# Fubarino_SD_v10.net
KiCad netlist of a schematic drawn in EAGLE
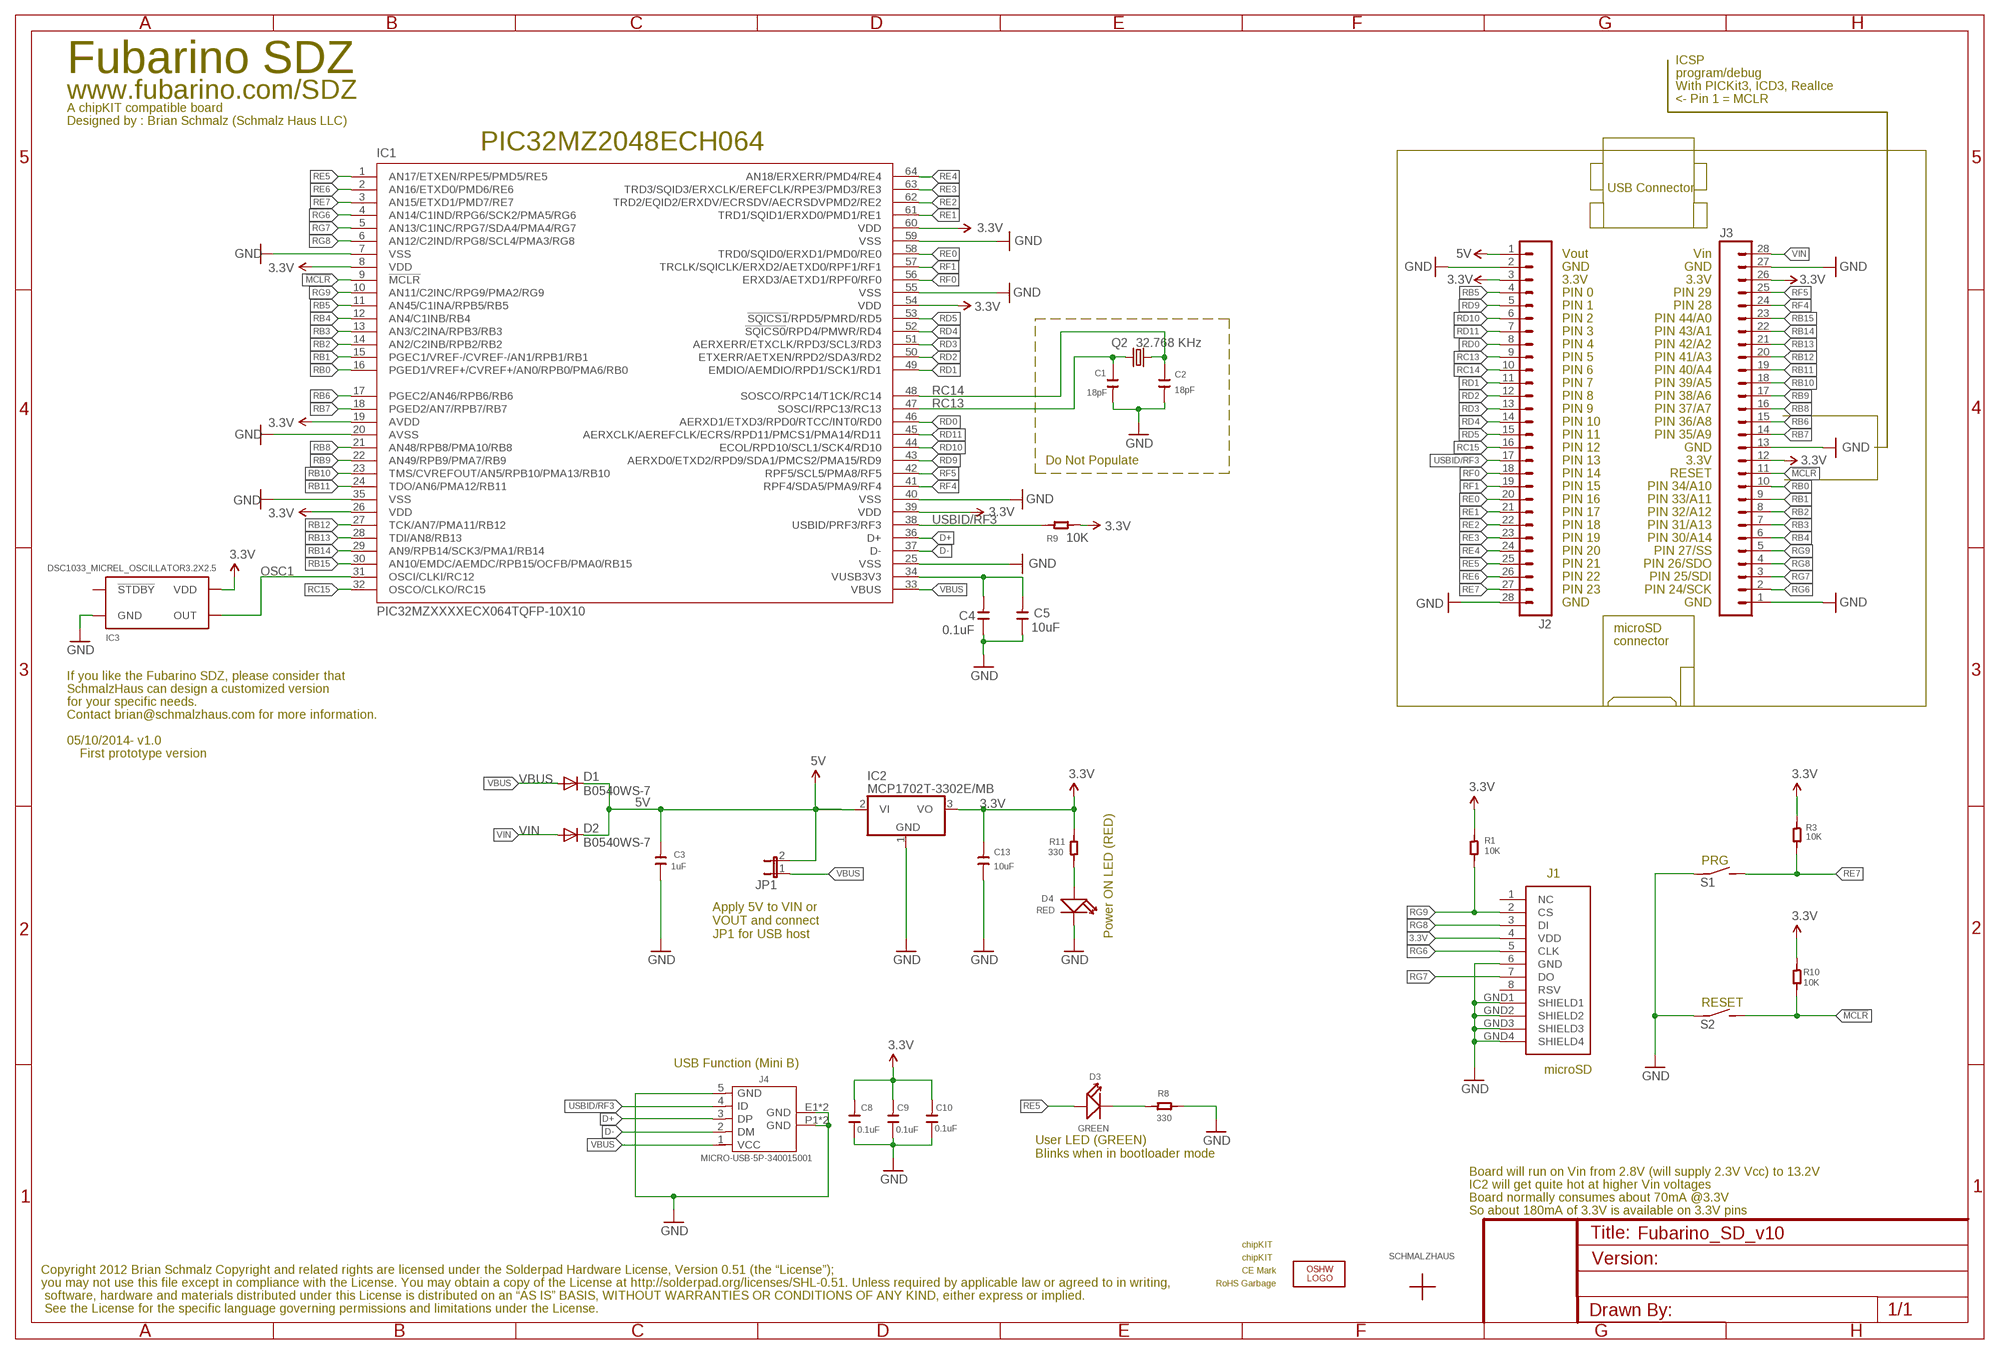
[diagram p0: schematic, sheet 1]

(export (version "E")
  (design (tool "Eeschema 10.0.6"))
  (components
    (comp (ref "C1")
      (value "18pF")
      (footprint "eagle-import:C0603")
      (libsource (lib "eagle-import") (part "C-0603"))
    )
    (comp (ref "C2")
      (value "18pF")
      (footprint "eagle-import:C0603")
      (libsource (lib "eagle-import") (part "C-0603"))
    )
    (comp (ref "C3")
      (value "1uF")
      (footprint "eagle-import:C0603")
      (libsource (lib "eagle-import") (part "C-0603"))
    )
    (comp (ref "C4")
      (value "0.1uF")
      (footprint "eagle-import:C0603")
      (libsource (lib "eagle-import") (part "C-0603"))
    )
    (comp (ref "C5")
      (value "10uF")
      (footprint "eagle-import:C0805")
      (libsource (lib "eagle-import") (part "C-0805"))
    )
    (comp (ref "C8")
      (value "0.1uF")
      (footprint "eagle-import:C0603")
      (libsource (lib "eagle-import") (part "C-0603"))
    )
    (comp (ref "C9")
      (value "0.1uF")
      (footprint "eagle-import:C0603")
      (libsource (lib "eagle-import") (part "C-0603"))
    )
    (comp (ref "C10")
      (value "0.1uF")
      (footprint "eagle-import:C0603")
      (libsource (lib "eagle-import") (part "C-0603"))
    )
    (comp (ref "C13")
      (value "10uF")
      (footprint "eagle-import:C0805")
      (libsource (lib "eagle-import") (part "C-0805"))
    )
    (comp (ref "D1")
      (value "B0540WS-7")
      (footprint "eagle-import:SOD-323")
      (libsource (lib "eagle-import") (part "DIODESOD"))
    )
    (comp (ref "D2")
      (value "B0540WS-7")
      (footprint "eagle-import:SOD-323")
      (libsource (lib "eagle-import") (part "DIODESOD"))
    )
    (comp (ref "D3")
      (value "GREEN")
      (footprint "eagle-import:LED0603")
      (libsource (lib "eagle-import") (part "LED"))
    )
    (comp (ref "D4")
      (value "RED")
      (footprint "eagle-import:LED0603")
      (libsource (lib "eagle-import") (part "LED"))
    )
    (comp (ref "IC1")
      (value "PIC32MZXXXXECX064TQFP-10X10")
      (footprint "eagle-import:TQFP64-10X10-SOLDERDAMS")
      (libsource (lib "eagle-import") (part "PIC32MZXXXXECX064TQFP-10X10"))
    )
    (comp (ref "IC2")
      (value "MCP1702T-3302E/MB")
      (footprint "eagle-import:SOT89")
      (libsource (lib "eagle-import") (part "MCP1703MB33"))
    )
    (comp (ref "IC3")
      (value "DSC1033_MICREL_OSCILLATOR3.2X2.5")
      (footprint "eagle-import:3.2X2.5_SILABS_OSC_DSC1033")
      (libsource (lib "eagle-import") (part "DSC1033_MICREL_OSCILLATOR3.2X2.5"))
    )
    (comp (ref "J1")
      (value "MICRO_SD_CARD_SOCKET")
      (footprint "eagle-import:SD-MMC_SOCKET-PP")
      (libsource (lib "eagle-import") (part "MICRO_SD_CARD_SOCKET"))
    )
    (comp (ref "J2")
      (value "M28USEPIN1")
      (footprint "eagle-import:1X28")
      (libsource (lib "eagle-import") (part "M28USEPIN1"))
    )
    (comp (ref "J3")
      (value "M28NOPIN1")
      (footprint "eagle-import:1X28_NO_PIN_1")
      (libsource (lib "eagle-import") (part "M28NOPIN1"))
    )
    (comp (ref "J4")
      (value "MICRO-USB-5P-340015001")
      (footprint "eagle-import:B-SMD-5P")
      (libsource (lib "eagle-import") (part "MICRO-USB-5P-340015001"))
    )
    (comp (ref "JP1")
      (value "JUMPER-2SMD-NO")
      (footprint "eagle-import:SJ_2S-NO")
      (libsource (lib "eagle-import") (part "JUMPER-2SMD-NO"))
    )
    (comp (ref "LOGO1")
      (value "OSHW_LOGO_8MILX0070-NT")
      (footprint "eagle-import:OSHW_8X70_NOTEXT")
      (libsource (lib "eagle-import") (part "OSHW_LOGO_8MILX0070-NT"))
    )
    (comp (ref "Q2")
      (value "32.768 KHz")
      (footprint "eagle-import:TC26H")
      (libsource (lib "eagle-import") (part "CRYSTALTC26H"))
    )
    (comp (ref "R1")
      (value "10K")
      (footprint "eagle-import:R0603")
      (libsource (lib "eagle-import") (part "R-0603"))
    )
    (comp (ref "R3")
      (value "10K")
      (footprint "eagle-import:R0603")
      (libsource (lib "eagle-import") (part "R-0603"))
    )
    (comp (ref "R8")
      (value "330")
      (footprint "eagle-import:R0603")
      (libsource (lib "eagle-import") (part "R-0603"))
    )
    (comp (ref "R9")
      (value "10K")
      (footprint "eagle-import:R0603")
      (libsource (lib "eagle-import") (part "R-0603"))
    )
    (comp (ref "R10")
      (value "10K")
      (footprint "eagle-import:R0603")
      (libsource (lib "eagle-import") (part "R-0603"))
    )
    (comp (ref "R11")
      (value "330")
      (footprint "eagle-import:R0603")
      (libsource (lib "eagle-import") (part "R-0603"))
    )
    (comp (ref "S1")
      (value "SWITCH")
      (footprint "eagle-import:SWITCH_KMR_SMT_TACT")
      (libsource (lib "eagle-import") (part "SWITCH"))
    )
    (comp (ref "S2")
      (value "SWITCH")
      (footprint "eagle-import:SWITCH_KMR_SMT_TACT")
      (libsource (lib "eagle-import") (part "SWITCH"))
    )
    (comp (ref "U$1")
      (value "SCHMALZHAUSSCHMALZHAUS_SMALL")
      (footprint "eagle-import:SCHMALZHAUS_SMALL")
      (libsource (lib "eagle-import") (part "SCHMALZHAUSSCHMALZHAUS_SMALL"))
    )
    (comp (ref "U$2")
      (value "CE_MARK5MM")
      (footprint "eagle-import:CE_5MM")
      (libsource (lib "eagle-import") (part "CE_MARK5MM"))
    )
    (comp (ref "U$3")
      (value "ROHS_GARBAGE")
      (footprint "eagle-import:ROHS_GARBAGE_5MM")
      (libsource (lib "eagle-import") (part "ROHS_GARBAGE"))
    )
    (comp (ref "U$4")
      (value "CHIPKIT2MM")
      (footprint "eagle-import:CHIPKIT_2MM")
      (libsource (lib "eagle-import") (part "CHIPKIT2MM"))
    )
    (comp (ref "U$5")
      (value "CHIPKIT2MM")
      (footprint "eagle-import:CHIPKIT_2MM")
      (libsource (lib "eagle-import") (part "CHIPKIT2MM"))
    )
  )
  (nets
    (net (code "1") (name "/OSC1") (class "Default")
      (node (ref "IC1") (pin "31") (pinfunction "OSCI/CLKI/RC12_31") (pintype "bidirectional"))
      (node (ref "IC3") (pin "P$3") (pinfunction "OUT_P$3") (pintype "output"))
    )
    (net (code "2") (name "/~{MCLR}") (class "Default")
      (node (ref "IC1") (pin "9") (pinfunction "~{MCLR}_9") (pintype "input"))
      (node (ref "J3") (pin "11") (pinfunction "11_11") (pintype "passive"))
      (node (ref "R10") (pin "2") (pinfunction "2_2") (pintype "bidirectional"))
      (node (ref "S2") (pin "P$3") (pinfunction "2_P$3") (pintype "passive"))
      (node (ref "S2") (pin "P$4") (pinfunction "2_P$4") (pintype "passive"))
    )
    (net (code "3") (name "3.3V") (class "Default")
      (node (ref "C10") (pin "1") (pinfunction "1_1") (pintype "bidirectional"))
      (node (ref "C13") (pin "1") (pinfunction "1_1") (pintype "bidirectional"))
      (node (ref "C8") (pin "1") (pinfunction "1_1") (pintype "bidirectional"))
      (node (ref "C9") (pin "1") (pinfunction "1_1") (pintype "bidirectional"))
      (node (ref "IC1") (pin "19") (pinfunction "AVDD_19") (pintype "power_in"))
      (node (ref "IC1") (pin "26") (pinfunction "VDD_26") (pintype "power_in"))
      (node (ref "IC1") (pin "39") (pinfunction "VDD_39") (pintype "power_in"))
      (node (ref "IC1") (pin "54") (pinfunction "VDD_54") (pintype "power_in"))
      (node (ref "IC1") (pin "60") (pinfunction "VDD_60") (pintype "power_in"))
      (node (ref "IC1") (pin "8") (pinfunction "VDD_8") (pintype "power_in"))
      (node (ref "IC2") (pin "3") (pinfunction "VO_3") (pintype "passive"))
      (node (ref "IC3") (pin "P$4") (pinfunction "VDD_P$4") (pintype "power_in"))
      (node (ref "J1") (pin "4") (pinfunction "VDD_4") (pintype "bidirectional"))
      (node (ref "J2") (pin "3") (pinfunction "3_3") (pintype "passive"))
      (node (ref "J3") (pin "12") (pinfunction "12_12") (pintype "passive"))
      (node (ref "J3") (pin "26") (pinfunction "26_26") (pintype "passive"))
      (node (ref "R1") (pin "1") (pinfunction "1_1") (pintype "bidirectional"))
      (node (ref "R10") (pin "1") (pinfunction "1_1") (pintype "bidirectional"))
      (node (ref "R11") (pin "2") (pinfunction "2_2") (pintype "bidirectional"))
      (node (ref "R3") (pin "1") (pinfunction "1_1") (pintype "bidirectional"))
      (node (ref "R9") (pin "2") (pinfunction "2_2") (pintype "bidirectional"))
    )
    (net (code "4") (name "5V") (class "Default")
      (node (ref "C3") (pin "1") (pinfunction "1_1") (pintype "bidirectional"))
      (node (ref "D1") (pin "1") (pinfunction "C_1") (pintype "passive"))
      (node (ref "D2") (pin "1") (pinfunction "C_1") (pintype "passive"))
      (node (ref "IC2") (pin "2") (pinfunction "VI_2") (pintype "input"))
      (node (ref "IC2") (pin "2@1") (pinfunction "VI1_2@1") (pintype "input"))
      (node (ref "J2") (pin "1") (pinfunction "1_1") (pintype "passive"))
      (node (ref "JP1") (pin "2") (pinfunction "2_2") (pintype "passive"))
    )
    (net (code "5") (name "D+") (class "Default")
      (node (ref "IC1") (pin "36") (pinfunction "D+_36") (pintype "bidirectional"))
      (node (ref "J4") (pin "3") (pinfunction "DP_3") (pintype "bidirectional"))
    )
    (net (code "6") (name "D-") (class "Default")
      (node (ref "IC1") (pin "37") (pinfunction "D-_37") (pintype "bidirectional"))
      (node (ref "J4") (pin "2") (pinfunction "DM_2") (pintype "bidirectional"))
    )
    (net (code "7") (name "GND") (class "Default")
      (node (ref "C1") (pin "1") (pinfunction "1_1") (pintype "bidirectional"))
      (node (ref "C10") (pin "2") (pinfunction "2_2") (pintype "bidirectional"))
      (node (ref "C13") (pin "2") (pinfunction "2_2") (pintype "bidirectional"))
      (node (ref "C2") (pin "1") (pinfunction "1_1") (pintype "bidirectional"))
      (node (ref "C3") (pin "2") (pinfunction "2_2") (pintype "bidirectional"))
      (node (ref "C4") (pin "2") (pinfunction "2_2") (pintype "bidirectional"))
      (node (ref "C5") (pin "2") (pinfunction "2_2") (pintype "bidirectional"))
      (node (ref "C8") (pin "2") (pinfunction "2_2") (pintype "bidirectional"))
      (node (ref "C9") (pin "2") (pinfunction "2_2") (pintype "bidirectional"))
      (node (ref "D4") (pin "-") (pinfunction "-_-") (pintype "passive"))
      (node (ref "IC1") (pin "20") (pinfunction "AVSS_20") (pintype "power_in"))
      (node (ref "IC1") (pin "25") (pinfunction "VSS_25") (pintype "power_in"))
      (node (ref "IC1") (pin "35") (pinfunction "VSS_35") (pintype "power_in"))
      (node (ref "IC1") (pin "40") (pinfunction "VSS_40") (pintype "power_in"))
      (node (ref "IC1") (pin "55") (pinfunction "VSS_55") (pintype "power_in"))
      (node (ref "IC1") (pin "59") (pinfunction "VSS_59") (pintype "power_in"))
      (node (ref "IC1") (pin "7") (pinfunction "VSS_7") (pintype "power_in"))
      (node (ref "IC2") (pin "1") (pinfunction "GND_1") (pintype "passive"))
      (node (ref "IC3") (pin "P$2") (pinfunction "GND_P$2") (pintype "power_in"))
      (node (ref "J1") (pin "6") (pinfunction "GND_6") (pintype "bidirectional"))
      (node (ref "J1") (pin "GND1") (pinfunction "SHIELD1_GND1") (pintype "bidirectional"))
      (node (ref "J1") (pin "GND2") (pinfunction "SHIELD2_GND2") (pintype "bidirectional"))
      (node (ref "J1") (pin "GND3") (pinfunction "SHIELD3_GND3") (pintype "bidirectional"))
      (node (ref "J1") (pin "GND4") (pinfunction "SHIELD4_GND4") (pintype "bidirectional"))
      (node (ref "J2") (pin "2") (pinfunction "2_2") (pintype "passive"))
      (node (ref "J2") (pin "28") (pinfunction "28_28") (pintype "passive"))
      (node (ref "J3") (pin "1") (pinfunction "1_1") (pintype "passive"))
      (node (ref "J3") (pin "13") (pinfunction "13_13") (pintype "passive"))
      (node (ref "J3") (pin "27") (pinfunction "27_27") (pintype "passive"))
      (node (ref "J4") (pin "5") (pinfunction "GND_5") (pintype "bidirectional"))
      (node (ref "J4") (pin "E1") (pinfunction "GND_E1") (pintype "bidirectional"))
      (node (ref "J4") (pin "E2") (pinfunction "GND_E2") (pintype "bidirectional"))
      (node (ref "J4") (pin "P1") (pinfunction "GND_P1") (pintype "bidirectional"))
      (node (ref "J4") (pin "P2") (pinfunction "GND_P2") (pintype "bidirectional"))
      (node (ref "R8") (pin "2") (pinfunction "2_2") (pintype "bidirectional"))
      (node (ref "S1") (pin "P$1") (pinfunction "1_P$1") (pintype "passive"))
      (node (ref "S1") (pin "P$2") (pinfunction "1_P$2") (pintype "passive"))
      (node (ref "S2") (pin "P$1") (pinfunction "1_P$1") (pintype "passive"))
      (node (ref "S2") (pin "P$2") (pinfunction "1_P$2") (pintype "passive"))
    )
    (net (code "8") (name "Net-(D3-Pad-)") (class "Default")
      (node (ref "D3") (pin "-") (pinfunction "-_-") (pintype "passive"))
      (node (ref "R8") (pin "1") (pinfunction "1_1") (pintype "bidirectional"))
    )
    (net (code "9") (name "Net-(D4-Pad+)") (class "Default")
      (node (ref "D4") (pin "+") (pinfunction "+_+") (pintype "passive"))
      (node (ref "R11") (pin "1") (pinfunction "1_1") (pintype "bidirectional"))
    )
    (net (code "10") (name "Net-(IC1-VUSB3V3)") (class "Default")
      (node (ref "C4") (pin "1") (pinfunction "1_1") (pintype "bidirectional"))
      (node (ref "C5") (pin "1") (pinfunction "1_1") (pintype "bidirectional"))
      (node (ref "IC1") (pin "34") (pinfunction "VUSB3V3_34") (pintype "power_in"))
    )
    (net (code "11") (name "RB0") (class "Default")
      (node (ref "IC1") (pin "16") (pinfunction "PGED1/VREF+/CVREF+/AN0/RPB0/PMA6/RB0_16") (pintype "bidirectional"))
      (node (ref "J3") (pin "10") (pinfunction "10_10") (pintype "passive"))
    )
    (net (code "12") (name "RB1") (class "Default")
      (node (ref "IC1") (pin "15") (pinfunction "PGEC1/VREF-/CVREF-/AN1/RPB1/RB1_15") (pintype "bidirectional"))
      (node (ref "J3") (pin "9") (pinfunction "9_9") (pintype "passive"))
    )
    (net (code "13") (name "RB2") (class "Default")
      (node (ref "IC1") (pin "14") (pinfunction "AN2/C2INB/RPB2/RB2_14") (pintype "bidirectional"))
      (node (ref "J3") (pin "8") (pinfunction "8_8") (pintype "passive"))
    )
    (net (code "14") (name "RB3") (class "Default")
      (node (ref "IC1") (pin "13") (pinfunction "AN3/C2INA/RPB3/RB3_13") (pintype "bidirectional"))
      (node (ref "J3") (pin "7") (pinfunction "7_7") (pintype "passive"))
    )
    (net (code "15") (name "RB4") (class "Default")
      (node (ref "IC1") (pin "12") (pinfunction "AN4/C1INB/RB4_12") (pintype "bidirectional"))
      (node (ref "J3") (pin "6") (pinfunction "6_6") (pintype "passive"))
    )
    (net (code "16") (name "RB5") (class "Default")
      (node (ref "IC1") (pin "11") (pinfunction "AN45/C1INA/RPB5/RB5_11") (pintype "bidirectional"))
      (node (ref "J2") (pin "4") (pinfunction "4_4") (pintype "passive"))
    )
    (net (code "17") (name "RB6") (class "Default")
      (node (ref "IC1") (pin "17") (pinfunction "PGEC2/AN46/RPB6/RB6_17") (pintype "bidirectional"))
      (node (ref "J3") (pin "15") (pinfunction "15_15") (pintype "passive"))
    )
    (net (code "18") (name "RB7") (class "Default")
      (node (ref "IC1") (pin "18") (pinfunction "PGED2/AN7/RPB7/RB7_18") (pintype "bidirectional"))
      (node (ref "J3") (pin "14") (pinfunction "14_14") (pintype "passive"))
    )
    (net (code "19") (name "RB8") (class "Default")
      (node (ref "IC1") (pin "21") (pinfunction "AN48/RPB8/PMA10/RB8_21") (pintype "bidirectional"))
      (node (ref "J3") (pin "16") (pinfunction "16_16") (pintype "passive"))
    )
    (net (code "20") (name "RB9") (class "Default")
      (node (ref "IC1") (pin "22") (pinfunction "AN49/RPB9/PMA7/RB9_22") (pintype "bidirectional"))
      (node (ref "J3") (pin "17") (pinfunction "17_17") (pintype "passive"))
    )
    (net (code "21") (name "RB10") (class "Default")
      (node (ref "IC1") (pin "23") (pinfunction "TMS/CVREFOUT/AN5/RPB10/PMA13/RB10_23") (pintype "bidirectional"))
      (node (ref "J3") (pin "18") (pinfunction "18_18") (pintype "passive"))
    )
    (net (code "22") (name "RB11") (class "Default")
      (node (ref "IC1") (pin "24") (pinfunction "TDO/AN6/PMA12/RB11_24") (pintype "bidirectional"))
      (node (ref "J3") (pin "19") (pinfunction "19_19") (pintype "passive"))
    )
    (net (code "23") (name "RB12") (class "Default")
      (node (ref "IC1") (pin "27") (pinfunction "TCK/AN7/PMA11/RB12_27") (pintype "bidirectional"))
      (node (ref "J3") (pin "20") (pinfunction "20_20") (pintype "passive"))
    )
    (net (code "24") (name "RB13") (class "Default")
      (node (ref "IC1") (pin "28") (pinfunction "TDI/AN8/RB13_28") (pintype "bidirectional"))
      (node (ref "J3") (pin "21") (pinfunction "21_21") (pintype "passive"))
    )
    (net (code "25") (name "RB14") (class "Default")
      (node (ref "IC1") (pin "29") (pinfunction "AN9/RPB14/SCK3/PMA1/RB14_29") (pintype "bidirectional"))
      (node (ref "J3") (pin "22") (pinfunction "22_22") (pintype "passive"))
    )
    (net (code "26") (name "RB15") (class "Default")
      (node (ref "IC1") (pin "30") (pinfunction "AN10/EMDC/AEMDC/RPB15/OCFB/PMA0/RB15_30") (pintype "bidirectional"))
      (node (ref "J3") (pin "23") (pinfunction "23_23") (pintype "passive"))
    )
    (net (code "27") (name "RC13") (class "Default")
      (node (ref "C1") (pin "2") (pinfunction "2_2") (pintype "bidirectional"))
      (node (ref "IC1") (pin "47") (pinfunction "SOSCI/RPC13/RC13_47") (pintype "bidirectional"))
      (node (ref "J2") (pin "9") (pinfunction "9_9") (pintype "passive"))
      (node (ref "Q2") (pin "1") (pinfunction "1_1") (pintype "passive"))
    )
    (net (code "28") (name "RC14") (class "Default")
      (node (ref "C2") (pin "2") (pinfunction "2_2") (pintype "bidirectional"))
      (node (ref "IC1") (pin "48") (pinfunction "SOSCO/RPC14/T1CK/RC14_48") (pintype "bidirectional"))
      (node (ref "J2") (pin "10") (pinfunction "10_10") (pintype "passive"))
      (node (ref "Q2") (pin "2") (pinfunction "2_2") (pintype "passive"))
    )
    (net (code "29") (name "RC15") (class "Default")
      (node (ref "IC1") (pin "32") (pinfunction "OSCO/CLKO/RC15_32") (pintype "bidirectional"))
      (node (ref "J2") (pin "16") (pinfunction "16_16") (pintype "passive"))
    )
    (net (code "30") (name "RD0") (class "Default")
      (node (ref "IC1") (pin "46") (pinfunction "AERXD1/ETXD3/RPD0/RTCC/INT0/RD0_46") (pintype "bidirectional"))
      (node (ref "J2") (pin "8") (pinfunction "8_8") (pintype "passive"))
    )
    (net (code "31") (name "RD1") (class "Default")
      (node (ref "IC1") (pin "49") (pinfunction "EMDIO/AEMDIO/RPD1/SCK1/RD1_49") (pintype "bidirectional"))
      (node (ref "J2") (pin "11") (pinfunction "11_11") (pintype "passive"))
    )
    (net (code "32") (name "RD2") (class "Default")
      (node (ref "IC1") (pin "50") (pinfunction "ETXERR/AETXEN/RPD2/SDA3/RD2_50") (pintype "bidirectional"))
      (node (ref "J2") (pin "12") (pinfunction "12_12") (pintype "passive"))
    )
    (net (code "33") (name "RD3") (class "Default")
      (node (ref "IC1") (pin "51") (pinfunction "AERXERR/ETXCLK/RPD3/SCL3/RD3_51") (pintype "bidirectional"))
      (node (ref "J2") (pin "13") (pinfunction "13_13") (pintype "passive"))
    )
    (net (code "34") (name "RD4") (class "Default")
      (node (ref "IC1") (pin "52") (pinfunction "~{SQICS0}/RPD4/PMWR/RD4_52") (pintype "bidirectional"))
      (node (ref "J2") (pin "14") (pinfunction "14_14") (pintype "passive"))
    )
    (net (code "35") (name "RD5") (class "Default")
      (node (ref "IC1") (pin "53") (pinfunction "~{SQICS1}/RPD5/PMRD/RD5_53") (pintype "bidirectional"))
      (node (ref "J2") (pin "15") (pinfunction "15_15") (pintype "passive"))
    )
    (net (code "36") (name "RD9") (class "Default")
      (node (ref "IC1") (pin "43") (pinfunction "AERXD0/ETXD2/RPD9/SDA1/PMCS2/PMA15/RD9_43") (pintype "bidirectional"))
      (node (ref "J2") (pin "5") (pinfunction "5_5") (pintype "passive"))
    )
    (net (code "37") (name "RD10") (class "Default")
      (node (ref "IC1") (pin "44") (pinfunction "ECOL/RPD10/SCL1/SCK4/RD10_44") (pintype "bidirectional"))
      (node (ref "J2") (pin "6") (pinfunction "6_6") (pintype "passive"))
    )
    (net (code "38") (name "RD11") (class "Default")
      (node (ref "IC1") (pin "45") (pinfunction "AERXCLK/AEREFCLK/ECRS/RPD11/PMCS1/PMA14/RD11_45") (pintype "bidirectional"))
      (node (ref "J2") (pin "7") (pinfunction "7_7") (pintype "passive"))
    )
    (net (code "39") (name "RE0") (class "Default")
      (node (ref "IC1") (pin "58") (pinfunction "TRD0/SQID0/ERXD1/PMD0/RE0_58") (pintype "bidirectional"))
      (node (ref "J2") (pin "20") (pinfunction "20_20") (pintype "passive"))
    )
    (net (code "40") (name "RE1") (class "Default")
      (node (ref "IC1") (pin "61") (pinfunction "TRD1/SQID1/ERXD0/PMD1/RE1_61") (pintype "bidirectional"))
      (node (ref "J2") (pin "21") (pinfunction "21_21") (pintype "passive"))
    )
    (net (code "41") (name "RE2") (class "Default")
      (node (ref "IC1") (pin "62") (pinfunction "TRD2/EQID2/ERXDV/ECRSDV/AECRSDVPMD2/RE2_62") (pintype "bidirectional"))
      (node (ref "J2") (pin "22") (pinfunction "22_22") (pintype "passive"))
    )
    (net (code "42") (name "RE3") (class "Default")
      (node (ref "IC1") (pin "63") (pinfunction "TRD3/SQID3/ERXCLK/EREFCLK/RPE3/PMD3/RE3_63") (pintype "bidirectional"))
      (node (ref "J2") (pin "23") (pinfunction "23_23") (pintype "passive"))
    )
    (net (code "43") (name "RE4") (class "Default")
      (node (ref "IC1") (pin "64") (pinfunction "AN18/ERXERR/PMD4/RE4_64") (pintype "bidirectional"))
      (node (ref "J2") (pin "24") (pinfunction "24_24") (pintype "passive"))
    )
    (net (code "44") (name "RE5") (class "Default")
      (node (ref "D3") (pin "+") (pinfunction "+_+") (pintype "passive"))
      (node (ref "IC1") (pin "1") (pinfunction "AN17/ETXEN/RPE5/PMD5/RE5_1") (pintype "bidirectional"))
      (node (ref "J2") (pin "25") (pinfunction "25_25") (pintype "passive"))
    )
    (net (code "45") (name "RE6") (class "Default")
      (node (ref "IC1") (pin "2") (pinfunction "AN16/ETXD0/PMD6/RE6_2") (pintype "bidirectional"))
      (node (ref "J2") (pin "26") (pinfunction "26_26") (pintype "passive"))
    )
    (net (code "46") (name "RE7") (class "Default")
      (node (ref "IC1") (pin "3") (pinfunction "AN15/ETXD1/PMD7/RE7_3") (pintype "bidirectional"))
      (node (ref "J2") (pin "27") (pinfunction "27_27") (pintype "passive"))
      (node (ref "R3") (pin "2") (pinfunction "2_2") (pintype "bidirectional"))
      (node (ref "S1") (pin "P$3") (pinfunction "2_P$3") (pintype "passive"))
      (node (ref "S1") (pin "P$4") (pinfunction "2_P$4") (pintype "passive"))
    )
    (net (code "47") (name "RF0") (class "Default")
      (node (ref "IC1") (pin "56") (pinfunction "ERXD3/AETXD1/RPF0/RF0_56") (pintype "bidirectional"))
      (node (ref "J2") (pin "18") (pinfunction "18_18") (pintype "passive"))
    )
    (net (code "48") (name "RF1") (class "Default")
      (node (ref "IC1") (pin "57") (pinfunction "TRCLK/SQICLK/ERXD2/AETXD0/RPF1/RF1_57") (pintype "bidirectional"))
      (node (ref "J2") (pin "19") (pinfunction "19_19") (pintype "passive"))
    )
    (net (code "49") (name "RF4") (class "Default")
      (node (ref "IC1") (pin "41") (pinfunction "RPF4/SDA5/PMA9/RF4_41") (pintype "bidirectional"))
      (node (ref "J3") (pin "24") (pinfunction "24_24") (pintype "passive"))
    )
    (net (code "50") (name "RF5") (class "Default")
      (node (ref "IC1") (pin "42") (pinfunction "RPF5/SCL5/PMA8/RF5_42") (pintype "bidirectional"))
      (node (ref "J3") (pin "25") (pinfunction "25_25") (pintype "passive"))
    )
    (net (code "51") (name "RG6") (class "Default")
      (node (ref "IC1") (pin "4") (pinfunction "AN14/C1IND/RPG6/SCK2/PMA5/RG6_4") (pintype "bidirectional"))
      (node (ref "J1") (pin "5") (pinfunction "CLK_5") (pintype "bidirectional"))
      (node (ref "J3") (pin "2") (pinfunction "2_2") (pintype "passive"))
    )
    (net (code "52") (name "RG7") (class "Default")
      (node (ref "IC1") (pin "5") (pinfunction "AN13/C1INC/RPG7/SDA4/PMA4/RG7_5") (pintype "bidirectional"))
      (node (ref "J1") (pin "7") (pinfunction "DO_7") (pintype "bidirectional"))
      (node (ref "J3") (pin "3") (pinfunction "3_3") (pintype "passive"))
    )
    (net (code "53") (name "RG8") (class "Default")
      (node (ref "IC1") (pin "6") (pinfunction "AN12/C2IND/RPG8/SCL4/PMA3/RG8_6") (pintype "bidirectional"))
      (node (ref "J1") (pin "3") (pinfunction "DI_3") (pintype "bidirectional"))
      (node (ref "J3") (pin "4") (pinfunction "4_4") (pintype "passive"))
    )
    (net (code "54") (name "RG9") (class "Default")
      (node (ref "IC1") (pin "10") (pinfunction "AN11/C2INC/RPG9/PMA2/RG9_10") (pintype "bidirectional"))
      (node (ref "J1") (pin "2") (pinfunction "CS_2") (pintype "bidirectional"))
      (node (ref "J3") (pin "5") (pinfunction "5_5") (pintype "passive"))
      (node (ref "R1") (pin "2") (pinfunction "2_2") (pintype "bidirectional"))
    )
    (net (code "55") (name "USBID{slash}RF3") (class "Default")
      (node (ref "IC1") (pin "38") (pinfunction "USBID/PRF3/RF3_38") (pintype "bidirectional"))
      (node (ref "J2") (pin "17") (pinfunction "17_17") (pintype "passive"))
      (node (ref "J4") (pin "4") (pinfunction "ID_4") (pintype "bidirectional"))
      (node (ref "R9") (pin "1") (pinfunction "1_1") (pintype "bidirectional"))
    )
    (net (code "56") (name "VBUS") (class "Default")
      (node (ref "D1") (pin "2") (pinfunction "A_2") (pintype "passive"))
      (node (ref "IC1") (pin "33") (pinfunction "VBUS_33") (pintype "input"))
      (node (ref "J4") (pin "1") (pinfunction "VCC_1") (pintype "bidirectional"))
      (node (ref "JP1") (pin "1") (pinfunction "1_1") (pintype "passive"))
    )
    (net (code "57") (name "VIN") (class "Default")
      (node (ref "D2") (pin "2") (pinfunction "A_2") (pintype "passive"))
      (node (ref "J3") (pin "28") (pinfunction "28_28") (pintype "passive"))
    )
    (net (code "58") (name "unconnected-(IC3-~{STDBY}-PadP$1)") (class "Default")
      (node (ref "IC3") (pin "P$1") (pinfunction "~{STDBY}_P$1") (pintype "input"))
    )
    (net (code "59") (name "unconnected-(J1-NC-Pad1)") (class "Default")
      (node (ref "J1") (pin "1") (pinfunction "NC_1") (pintype "bidirectional"))
    )
    (net (code "60") (name "unconnected-(J1-RSV-Pad8)") (class "Default")
      (node (ref "J1") (pin "8") (pinfunction "RSV_8") (pintype "bidirectional"))
    )
  )
)
